# SCH_Endurance_drone_8.net
KiCad netlist of a schematic drawn in EasyEDA
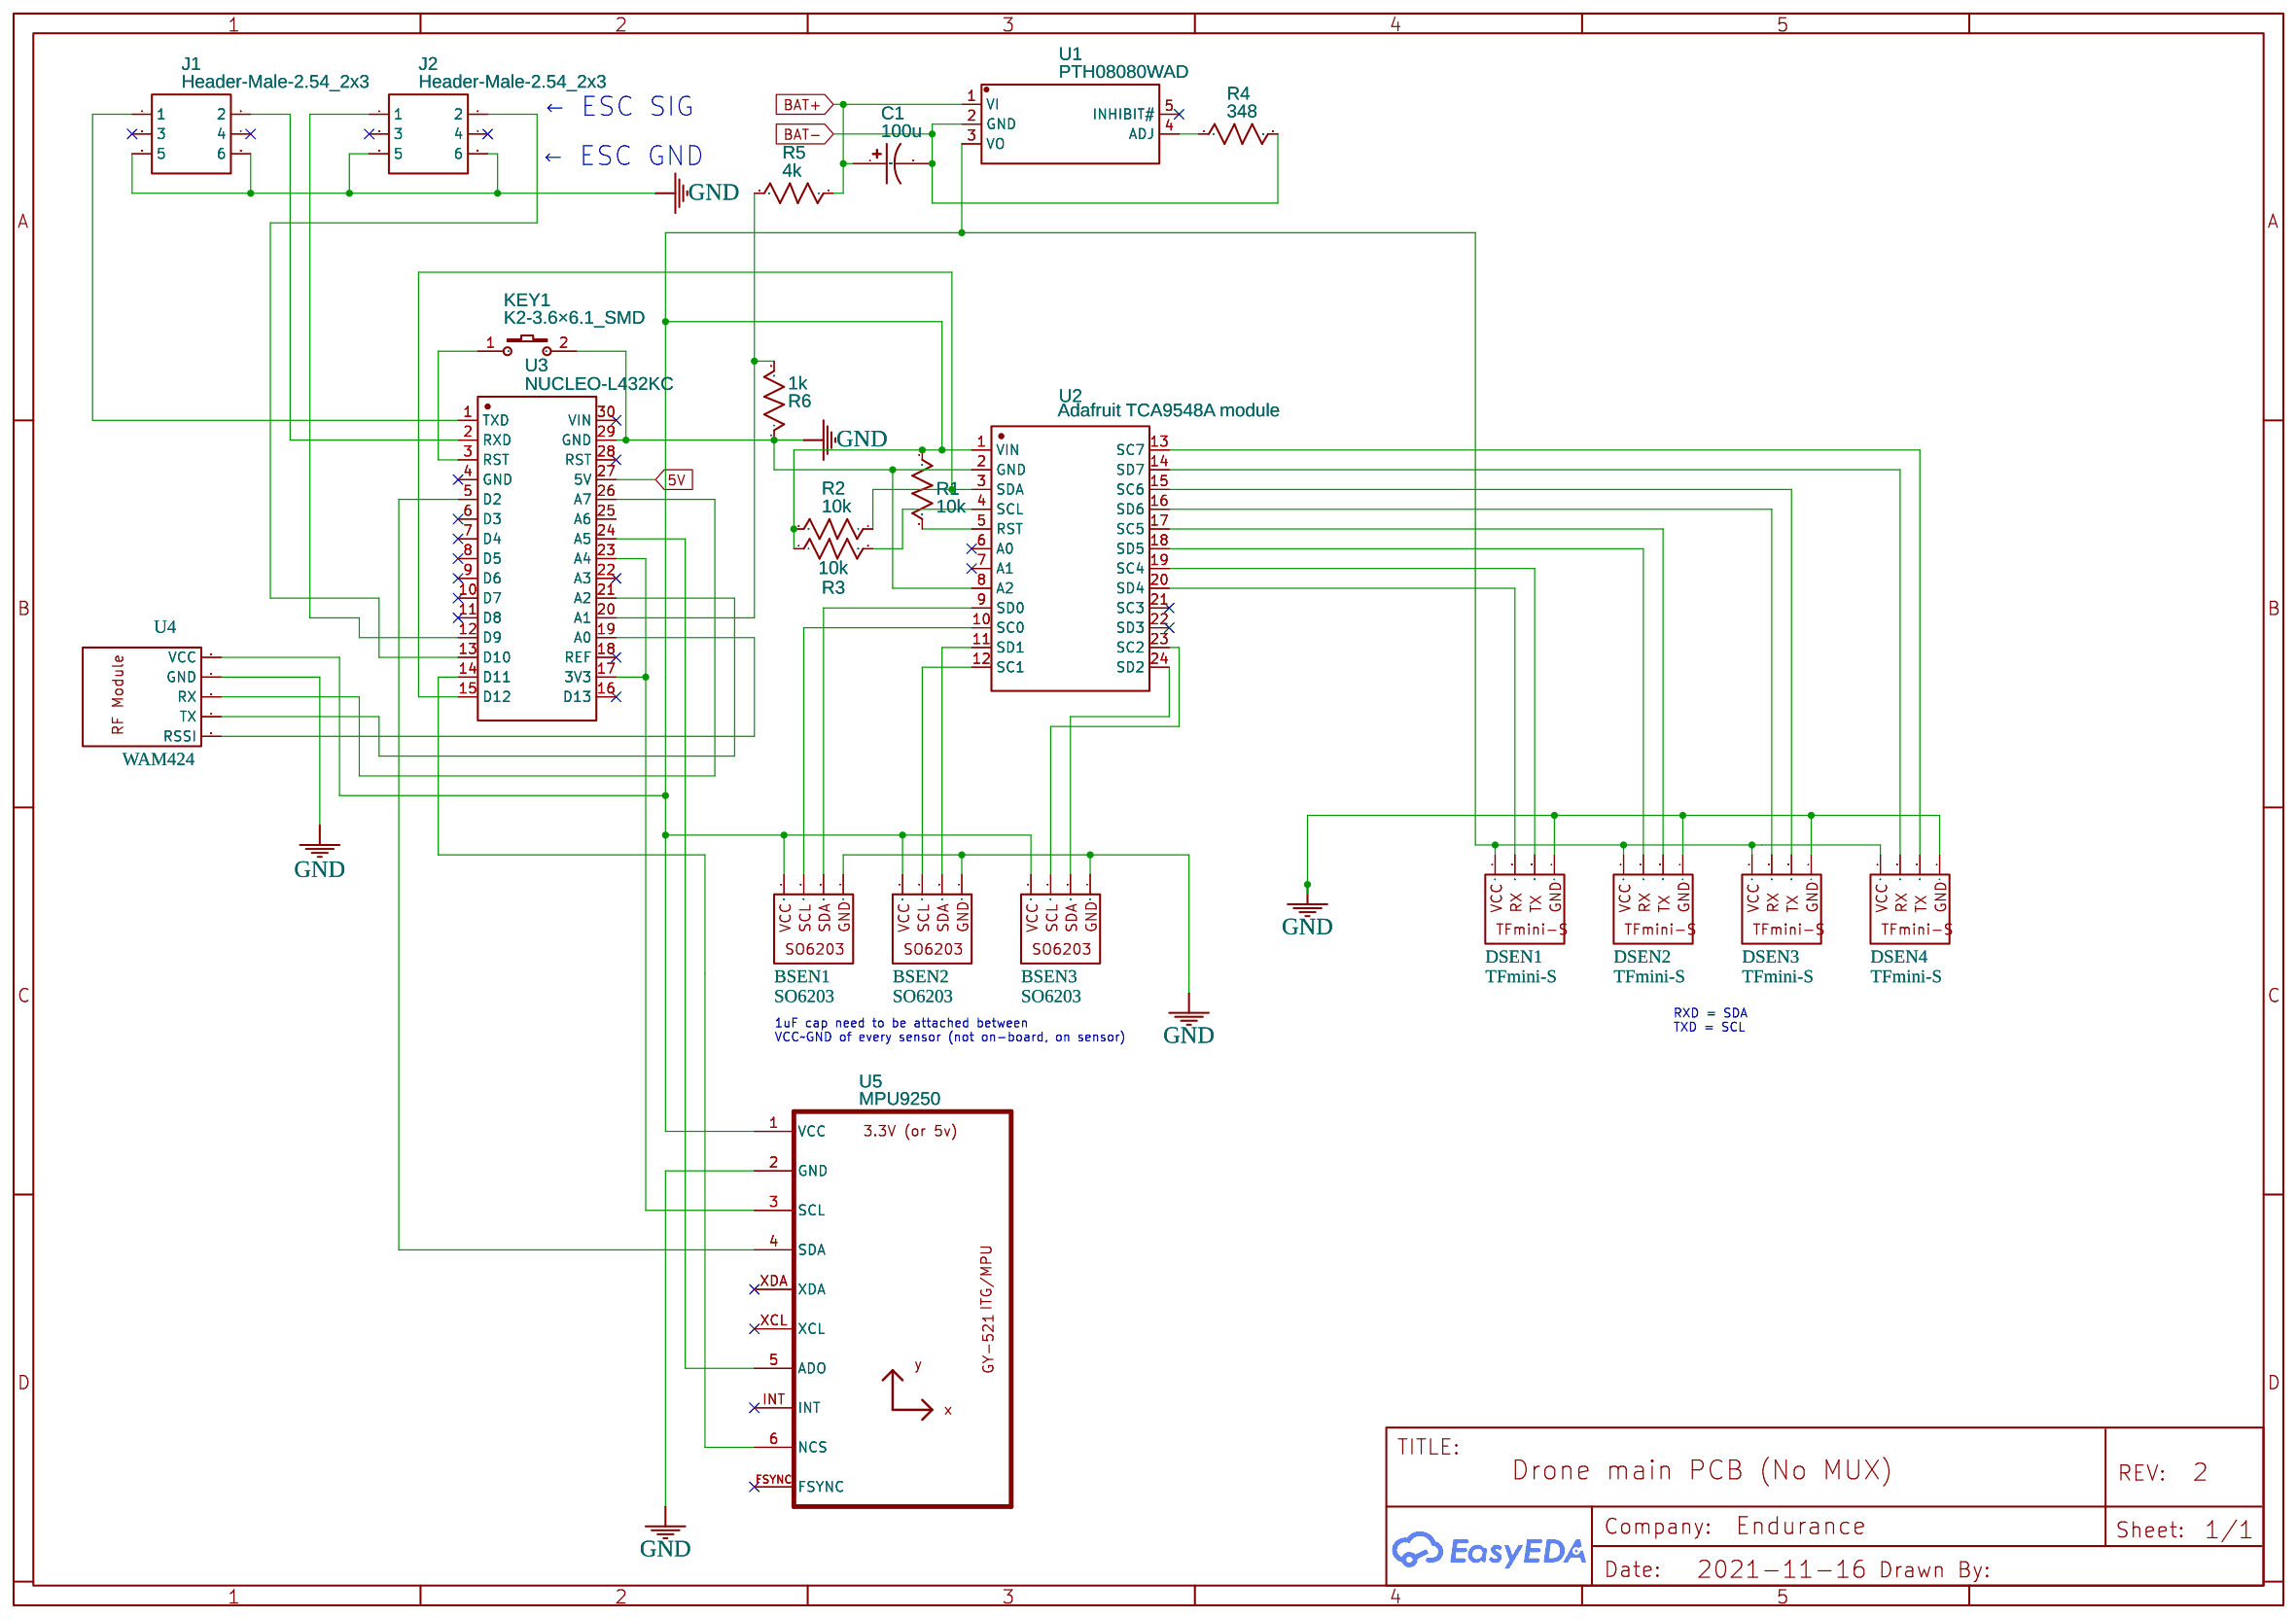
[diagram p0: schematic sheet]

(export (version "E")
  (design (tool "Eeschema 10.0.6"))
  (components
    (comp (ref "BSEN1") (value "SO6203") (libsource (lib "") (part "Unknown_405_-350")))
    (comp (ref "BSEN2") (value "SO6203") (libsource (lib "") (part "Unknown_465_-350")))
    (comp (ref "BSEN3") (value "SO6203") (libsource (lib "") (part "Unknown_530_-350")))
    (comp (ref "C1") (value "100u") (libsource (lib "") (part "C_Tan_SMD_A_US")))
    (comp (ref "DSEN1") (value "TFmini-S") (libsource (lib "") (part "Unknown_765_-360")))
    (comp (ref "DSEN2") (value "TFmini-S") (libsource (lib "") (part "Unknown_830_-360")))
    (comp (ref "DSEN3") (value "TFmini-S") (libsource (lib "") (part "Unknown_895_-360")))
    (comp (ref "DSEN4") (value "TFmini-S") (libsource (lib "") (part "Unknown_960_-360")))
    (comp (ref "J1")
      (value "Header-Male-2.54_2x3")
      (fields (field (name "BOM_Supplier Part") "C65114"))
      (libsource (lib "") (part "Header-Male-2.54_2x3"))
    )
    (comp (ref "J2")
      (value "Header-Male-2.54_2x3")
      (fields (field (name "BOM_Supplier Part") "C65114"))
      (libsource (lib "") (part "Header-Male-2.54_2x3"))
    )
    (comp (ref "KEY1")
      (value "K2-3.6×6.1_SMD")
      (fields
        (field (name "BOM_Manufacturer Part") "K2-1107ST-A4SW-06")
        (field (name "BOM_Supplier Part") "C118141")
      )
      (libsource (lib "") (part "K2-3.6×6.1_SMD"))
    )
    (comp (ref "R1") (value "10k") (libsource (lib "") (part "R_0603_US_2")))
    (comp (ref "R2") (value "10k") (libsource (lib "") (part "R_0603_US")))
    (comp (ref "R3") (value "10k") (libsource (lib "") (part "R_0603_US_3")))
    (comp (ref "R4") (value "348") (libsource (lib "") (part "R_0603_US_3")))
    (comp (ref "R5") (value "4k") (libsource (lib "") (part "R_0603_US")))
    (comp (ref "R6") (value "1k") (libsource (lib "") (part "R_0603_US_1")))
    (comp (ref "U1")
      (value "PTH08080WAD")
      (fields (field (name "BOM_Supplier Part") "C154927"))
      (libsource (lib "") (part "PTH08080WAD"))
    )
    (comp (ref "U2")
      (value "Adafruit TCA9548A module")
      (fields
        (field (name "BOM_Manufacturer Part") "TCA9548APWR")
        (field (name "BOM_Supplier Part") "C130026")
      )
      (libsource (lib "") (part "TCA9548APWR"))
    )
    (comp (ref "U3")
      (value "NUCLEO-L432KC")
      (fields (field (name "BOM_Supplier Part") "C94814"))
      (libsource (lib "") (part "NUCLEO-L432KC"))
    )
    (comp (ref "U4") (value "WAM424") (libsource (lib "") (part "Unknown_70_-460")))
    (comp (ref "U5") (value "MPU9250") (libsource (lib "") (part "MPU9250")))
  )
  (nets
    (net (code "1") (name "5V") (class "Default")
      (node (ref "U3") (pin "27") (pinfunction "5V_27") (pintype "unspecified"))
    )
    (net (code "2") (name "BAT+") (class "Default")
      (node (ref "C1") (pin "1") (pinfunction "1_1") (pintype "unspecified"))
      (node (ref "R5") (pin "1") (pinfunction "1_1") (pintype "unspecified"))
      (node (ref "U1") (pin "1") (pinfunction "VI_1") (pintype "unspecified"))
    )
    (net (code "3") (name "BAT-") (class "Default")
      (node (ref "C1") (pin "2") (pinfunction "2_2") (pintype "unspecified"))
      (node (ref "R4") (pin "2") (pinfunction "2_2") (pintype "unspecified"))
      (node (ref "U1") (pin "2") (pinfunction "GND_2") (pintype "unspecified"))
    )
    (net (code "4") (name "GND") (class "Default")
      (node (ref "BSEN1") (pin "4") (pinfunction "4_4") (pintype "unspecified"))
      (node (ref "BSEN2") (pin "4") (pinfunction "4_4") (pintype "unspecified"))
      (node (ref "BSEN3") (pin "4") (pinfunction "4_4") (pintype "unspecified"))
      (node (ref "DSEN1") (pin "4") (pinfunction "4_4") (pintype "unspecified"))
      (node (ref "DSEN2") (pin "4") (pinfunction "4_4") (pintype "unspecified"))
      (node (ref "DSEN3") (pin "4") (pinfunction "4_4") (pintype "unspecified"))
      (node (ref "DSEN4") (pin "4") (pinfunction "4_4") (pintype "unspecified"))
      (node (ref "J1") (pin "5") (pinfunction "5_5") (pintype "input"))
      (node (ref "J1") (pin "6") (pinfunction "6_6") (pintype "input"))
      (node (ref "J2") (pin "5") (pinfunction "5_5") (pintype "input"))
      (node (ref "J2") (pin "6") (pinfunction "6_6") (pintype "input"))
      (node (ref "KEY1") (pin "2") (pinfunction "2_2") (pintype "unspecified"))
      (node (ref "R6") (pin "1") (pinfunction "1_1") (pintype "unspecified"))
      (node (ref "U2") (pin "2") (pinfunction "GND_2") (pintype "unspecified"))
      (node (ref "U2") (pin "8") (pinfunction "A2_8") (pintype "unspecified"))
      (node (ref "U3") (pin "29") (pinfunction "GND_29") (pintype "unspecified"))
      (node (ref "U4") (pin "2") (pinfunction "GND_2") (pintype "unspecified"))
      (node (ref "U5") (pin "2") (pinfunction "GND_2") (pintype "bidirectional"))
    )
    (net (code "5") (name "Net-(KEY1-Pad1)") (class "Default")
      (node (ref "KEY1") (pin "1") (pinfunction "1_1") (pintype "unspecified"))
      (node (ref "U3") (pin "3") (pinfunction "RST_3") (pintype "unspecified"))
    )
    (net (code "6") (name "Net-(U1-ADJ)") (class "Default")
      (node (ref "R4") (pin "1") (pinfunction "1_1") (pintype "unspecified"))
      (node (ref "U1") (pin "4") (pinfunction "ADJ_4") (pintype "unspecified"))
    )
    (net (code "7") (name "Net-(U1-VO)") (class "Default")
      (node (ref "BSEN1") (pin "1") (pinfunction "1_1") (pintype "unspecified"))
      (node (ref "BSEN2") (pin "1") (pinfunction "1_1") (pintype "unspecified"))
      (node (ref "BSEN3") (pin "1") (pinfunction "1_1") (pintype "unspecified"))
      (node (ref "DSEN1") (pin "1") (pinfunction "1_1") (pintype "unspecified"))
      (node (ref "DSEN2") (pin "1") (pinfunction "1_1") (pintype "unspecified"))
      (node (ref "DSEN3") (pin "1") (pinfunction "1_1") (pintype "unspecified"))
      (node (ref "DSEN4") (pin "1") (pinfunction "1_1") (pintype "unspecified"))
      (node (ref "R1") (pin "1") (pinfunction "1_1") (pintype "unspecified"))
      (node (ref "R2") (pin "2") (pinfunction "2_2") (pintype "unspecified"))
      (node (ref "R3") (pin "1") (pinfunction "1_1") (pintype "unspecified"))
      (node (ref "U1") (pin "3") (pinfunction "VO_3") (pintype "unspecified"))
      (node (ref "U2") (pin "1") (pinfunction "VIN_1") (pintype "unspecified"))
      (node (ref "U4") (pin "1") (pinfunction "VCC_1") (pintype "unspecified"))
      (node (ref "U5") (pin "1") (pinfunction "VCC_1") (pintype "bidirectional"))
    )
    (net (code "8") (name "Net-(U2-RST)") (class "Default")
      (node (ref "R1") (pin "2") (pinfunction "2_2") (pintype "unspecified"))
      (node (ref "U2") (pin "5") (pinfunction "RST_5") (pintype "unspecified"))
    )
    (net (code "9") (name "Net-(U2-SC0)") (class "Default")
      (node (ref "BSEN1") (pin "2") (pinfunction "2_2") (pintype "unspecified"))
      (node (ref "U2") (pin "10") (pinfunction "SC0_10") (pintype "unspecified"))
    )
    (net (code "10") (name "Net-(U2-SC1)") (class "Default")
      (node (ref "BSEN2") (pin "2") (pinfunction "2_2") (pintype "unspecified"))
      (node (ref "U2") (pin "12") (pinfunction "SC1_12") (pintype "unspecified"))
    )
    (net (code "11") (name "Net-(U2-SC2)") (class "Default")
      (node (ref "BSEN3") (pin "2") (pinfunction "2_2") (pintype "unspecified"))
      (node (ref "U2") (pin "23") (pinfunction "SC2_23") (pintype "unspecified"))
    )
    (net (code "12") (name "Net-(U2-SC4)") (class "Default")
      (node (ref "DSEN1") (pin "3") (pinfunction "3_3") (pintype "unspecified"))
      (node (ref "U2") (pin "19") (pinfunction "SC4_19") (pintype "unspecified"))
    )
    (net (code "13") (name "Net-(U2-SC5)") (class "Default")
      (node (ref "DSEN2") (pin "3") (pinfunction "3_3") (pintype "unspecified"))
      (node (ref "U2") (pin "17") (pinfunction "SC5_17") (pintype "unspecified"))
    )
    (net (code "14") (name "Net-(U2-SC6)") (class "Default")
      (node (ref "DSEN3") (pin "3") (pinfunction "3_3") (pintype "unspecified"))
      (node (ref "U2") (pin "15") (pinfunction "SC6_15") (pintype "unspecified"))
    )
    (net (code "15") (name "Net-(U2-SC7)") (class "Default")
      (node (ref "DSEN4") (pin "3") (pinfunction "3_3") (pintype "unspecified"))
      (node (ref "U2") (pin "13") (pinfunction "SC7_13") (pintype "unspecified"))
    )
    (net (code "16") (name "Net-(U2-SCL)") (class "Default")
      (node (ref "R3") (pin "2") (pinfunction "2_2") (pintype "unspecified"))
      (node (ref "U2") (pin "4") (pinfunction "SCL_4") (pintype "unspecified"))
    )
    (net (code "17") (name "Net-(U2-SD0)") (class "Default")
      (node (ref "BSEN1") (pin "3") (pinfunction "3_3") (pintype "unspecified"))
      (node (ref "U2") (pin "9") (pinfunction "SD0_9") (pintype "unspecified"))
    )
    (net (code "18") (name "Net-(U2-SD1)") (class "Default")
      (node (ref "BSEN2") (pin "3") (pinfunction "3_3") (pintype "unspecified"))
      (node (ref "U2") (pin "11") (pinfunction "SD1_11") (pintype "unspecified"))
    )
    (net (code "19") (name "Net-(U2-SD2)") (class "Default")
      (node (ref "BSEN3") (pin "3") (pinfunction "3_3") (pintype "unspecified"))
      (node (ref "U2") (pin "24") (pinfunction "SD2_24") (pintype "unspecified"))
    )
    (net (code "20") (name "Net-(U2-SD4)") (class "Default")
      (node (ref "DSEN1") (pin "2") (pinfunction "2_2") (pintype "unspecified"))
      (node (ref "U2") (pin "20") (pinfunction "SD4_20") (pintype "unspecified"))
    )
    (net (code "21") (name "Net-(U2-SD5)") (class "Default")
      (node (ref "DSEN2") (pin "2") (pinfunction "2_2") (pintype "unspecified"))
      (node (ref "U2") (pin "18") (pinfunction "SD5_18") (pintype "unspecified"))
    )
    (net (code "22") (name "Net-(U2-SD6)") (class "Default")
      (node (ref "DSEN3") (pin "2") (pinfunction "2_2") (pintype "unspecified"))
      (node (ref "U2") (pin "16") (pinfunction "SD6_16") (pintype "unspecified"))
    )
    (net (code "23") (name "Net-(U2-SD7)") (class "Default")
      (node (ref "DSEN4") (pin "2") (pinfunction "2_2") (pintype "unspecified"))
      (node (ref "U2") (pin "14") (pinfunction "SD7_14") (pintype "unspecified"))
    )
    (net (code "24") (name "Net-(U2-SDA)") (class "Default")
      (node (ref "R2") (pin "1") (pinfunction "1_1") (pintype "unspecified"))
      (node (ref "U2") (pin "3") (pinfunction "SDA_3") (pintype "unspecified"))
      (node (ref "U3") (pin "15") (pinfunction "D12_15") (pintype "unspecified"))
    )
    (net (code "25") (name "Net-(U3-3V3)") (class "Default")
      (node (ref "U3") (pin "17") (pinfunction "3V3_17") (pintype "unspecified"))
      (node (ref "U3") (pin "23") (pinfunction "A4_23") (pintype "unspecified"))
      (node (ref "U5") (pin "3") (pinfunction "SCL_3") (pintype "bidirectional"))
    )
    (net (code "26") (name "Net-(U3-A0)") (class "Default")
      (node (ref "U3") (pin "19") (pinfunction "A0_19") (pintype "unspecified"))
      (node (ref "U4") (pin "5") (pinfunction "RSSI_5") (pintype "unspecified"))
    )
    (net (code "27") (name "Net-(U3-A1)") (class "Default")
      (node (ref "R5") (pin "2") (pinfunction "2_2") (pintype "unspecified"))
      (node (ref "R6") (pin "2") (pinfunction "2_2") (pintype "unspecified"))
      (node (ref "U3") (pin "20") (pinfunction "A1_20") (pintype "unspecified"))
    )
    (net (code "28") (name "Net-(U3-A2)") (class "Default")
      (node (ref "U3") (pin "21") (pinfunction "A2_21") (pintype "unspecified"))
      (node (ref "U4") (pin "4") (pinfunction "TX_4") (pintype "unspecified"))
    )
    (net (code "29") (name "Net-(U3-A5)") (class "Default")
      (node (ref "U3") (pin "24") (pinfunction "A5_24") (pintype "unspecified"))
      (node (ref "U5") (pin "5") (pinfunction "ADO_5") (pintype "bidirectional"))
    )
    (net (code "30") (name "Net-(U3-A7)") (class "Default")
      (node (ref "U3") (pin "26") (pinfunction "A7_26") (pintype "unspecified"))
      (node (ref "U4") (pin "3") (pinfunction "RX_3") (pintype "unspecified"))
    )
    (net (code "31") (name "Net-(U3-D2)") (class "Default")
      (node (ref "U3") (pin "5") (pinfunction "D2_5") (pintype "unspecified"))
      (node (ref "U5") (pin "4") (pinfunction "SDA_4") (pintype "bidirectional"))
    )
    (net (code "32") (name "Net-(U3-D9)") (class "Default")
      (node (ref "J2") (pin "1") (pinfunction "1_1") (pintype "input"))
      (node (ref "U3") (pin "12") (pinfunction "D9_12") (pintype "unspecified"))
    )
    (net (code "33") (name "Net-(U3-D10)") (class "Default")
      (node (ref "J2") (pin "2") (pinfunction "2_2") (pintype "input"))
      (node (ref "U3") (pin "13") (pinfunction "D10_13") (pintype "unspecified"))
    )
    (net (code "34") (name "Net-(U3-D11)") (class "Default")
      (node (ref "U3") (pin "14") (pinfunction "D11_14") (pintype "unspecified"))
      (node (ref "U5") (pin "6") (pinfunction "NCS_6") (pintype "bidirectional"))
    )
    (net (code "35") (name "Net-(U3-RXD)") (class "Default")
      (node (ref "J1") (pin "2") (pinfunction "2_2") (pintype "input"))
      (node (ref "U3") (pin "2") (pinfunction "RXD_2") (pintype "unspecified"))
    )
    (net (code "36") (name "Net-(U3-TXD)") (class "Default")
      (node (ref "J1") (pin "1") (pinfunction "1_1") (pintype "input"))
      (node (ref "U3") (pin "1") (pinfunction "TXD_1") (pintype "unspecified"))
    )
    (net (code "37") (name "unconnected-(J1-Pad3)") (class "Default")
      (node (ref "J1") (pin "3") (pinfunction "3_3") (pintype "input+no_connect"))
    )
    (net (code "38") (name "unconnected-(J1-Pad4)") (class "Default")
      (node (ref "J1") (pin "4") (pinfunction "4_4") (pintype "input+no_connect"))
    )
    (net (code "39") (name "unconnected-(J2-Pad3)") (class "Default")
      (node (ref "J2") (pin "3") (pinfunction "3_3") (pintype "input+no_connect"))
    )
    (net (code "40") (name "unconnected-(J2-Pad4)") (class "Default")
      (node (ref "J2") (pin "4") (pinfunction "4_4") (pintype "input+no_connect"))
    )
    (net (code "41") (name "unconnected-(U1-INHIBIT#-Pad5)") (class "Default")
      (node (ref "U1") (pin "5") (pinfunction "INHIBIT#_5") (pintype "unspecified+no_connect"))
    )
    (net (code "42") (name "unconnected-(U2-A0-Pad6)") (class "Default")
      (node (ref "U2") (pin "6") (pinfunction "A0_6") (pintype "unspecified+no_connect"))
    )
    (net (code "43") (name "unconnected-(U2-A1-Pad7)") (class "Default")
      (node (ref "U2") (pin "7") (pinfunction "A1_7") (pintype "unspecified+no_connect"))
    )
    (net (code "44") (name "unconnected-(U2-SC3-Pad21)") (class "Default")
      (node (ref "U2") (pin "21") (pinfunction "SC3_21") (pintype "unspecified+no_connect"))
    )
    (net (code "45") (name "unconnected-(U2-SD3-Pad22)") (class "Default")
      (node (ref "U2") (pin "22") (pinfunction "SD3_22") (pintype "unspecified+no_connect"))
    )
    (net (code "46") (name "unconnected-(U3-A3-Pad22)") (class "Default")
      (node (ref "U3") (pin "22") (pinfunction "A3_22") (pintype "unspecified+no_connect"))
    )
    (net (code "47") (name "unconnected-(U3-A6-Pad25)") (class "Default")
      (node (ref "U3") (pin "25") (pinfunction "A6_25") (pintype "unspecified"))
    )
    (net (code "48") (name "unconnected-(U3-D3-Pad6)") (class "Default")
      (node (ref "U3") (pin "6") (pinfunction "D3_6") (pintype "unspecified+no_connect"))
    )
    (net (code "49") (name "unconnected-(U3-D4-Pad7)") (class "Default")
      (node (ref "U3") (pin "7") (pinfunction "D4_7") (pintype "unspecified+no_connect"))
    )
    (net (code "50") (name "unconnected-(U3-D5-Pad8)") (class "Default")
      (node (ref "U3") (pin "8") (pinfunction "D5_8") (pintype "unspecified+no_connect"))
    )
    (net (code "51") (name "unconnected-(U3-D6-Pad9)") (class "Default")
      (node (ref "U3") (pin "9") (pinfunction "D6_9") (pintype "unspecified+no_connect"))
    )
    (net (code "52") (name "unconnected-(U3-D7-Pad10)") (class "Default")
      (node (ref "U3") (pin "10") (pinfunction "D7_10") (pintype "unspecified+no_connect"))
    )
    (net (code "53") (name "unconnected-(U3-D8-Pad11)") (class "Default")
      (node (ref "U3") (pin "11") (pinfunction "D8_11") (pintype "unspecified+no_connect"))
    )
    (net (code "54") (name "unconnected-(U3-D13-Pad16)") (class "Default")
      (node (ref "U3") (pin "16") (pinfunction "D13_16") (pintype "unspecified+no_connect"))
    )
    (net (code "55") (name "unconnected-(U3-GND-Pad4)") (class "Default")
      (node (ref "U3") (pin "4") (pinfunction "GND_4") (pintype "unspecified+no_connect"))
    )
    (net (code "56") (name "unconnected-(U3-REF-Pad18)") (class "Default")
      (node (ref "U3") (pin "18") (pinfunction "REF_18") (pintype "unspecified+no_connect"))
    )
    (net (code "57") (name "unconnected-(U3-RST-Pad28)") (class "Default")
      (node (ref "U3") (pin "28") (pinfunction "RST_28") (pintype "unspecified+no_connect"))
    )
    (net (code "58") (name "unconnected-(U3-VIN-Pad30)") (class "Default")
      (node (ref "U3") (pin "30") (pinfunction "VIN_30") (pintype "unspecified+no_connect"))
    )
    (net (code "59") (name "unconnected-(U5-PadFSYNC)") (class "Default")
      (node (ref "U5") (pin "FSYNC") (pinfunction "FSYNC_FSYNC") (pintype "bidirectional+no_connect"))
    )
    (net (code "60") (name "unconnected-(U5-PadINT)") (class "Default")
      (node (ref "U5") (pin "INT") (pinfunction "INT_INT") (pintype "bidirectional+no_connect"))
    )
    (net (code "61") (name "unconnected-(U5-PadXCL)") (class "Default")
      (node (ref "U5") (pin "XCL") (pinfunction "XCL_XCL") (pintype "bidirectional+no_connect"))
    )
    (net (code "62") (name "unconnected-(U5-PadXDA)") (class "Default")
      (node (ref "U5") (pin "XDA") (pinfunction "XDA_XDA") (pintype "bidirectional+no_connect"))
    )
  )
)
